# Power.net
KiCad netlist of a schematic drawn in Altium Designer
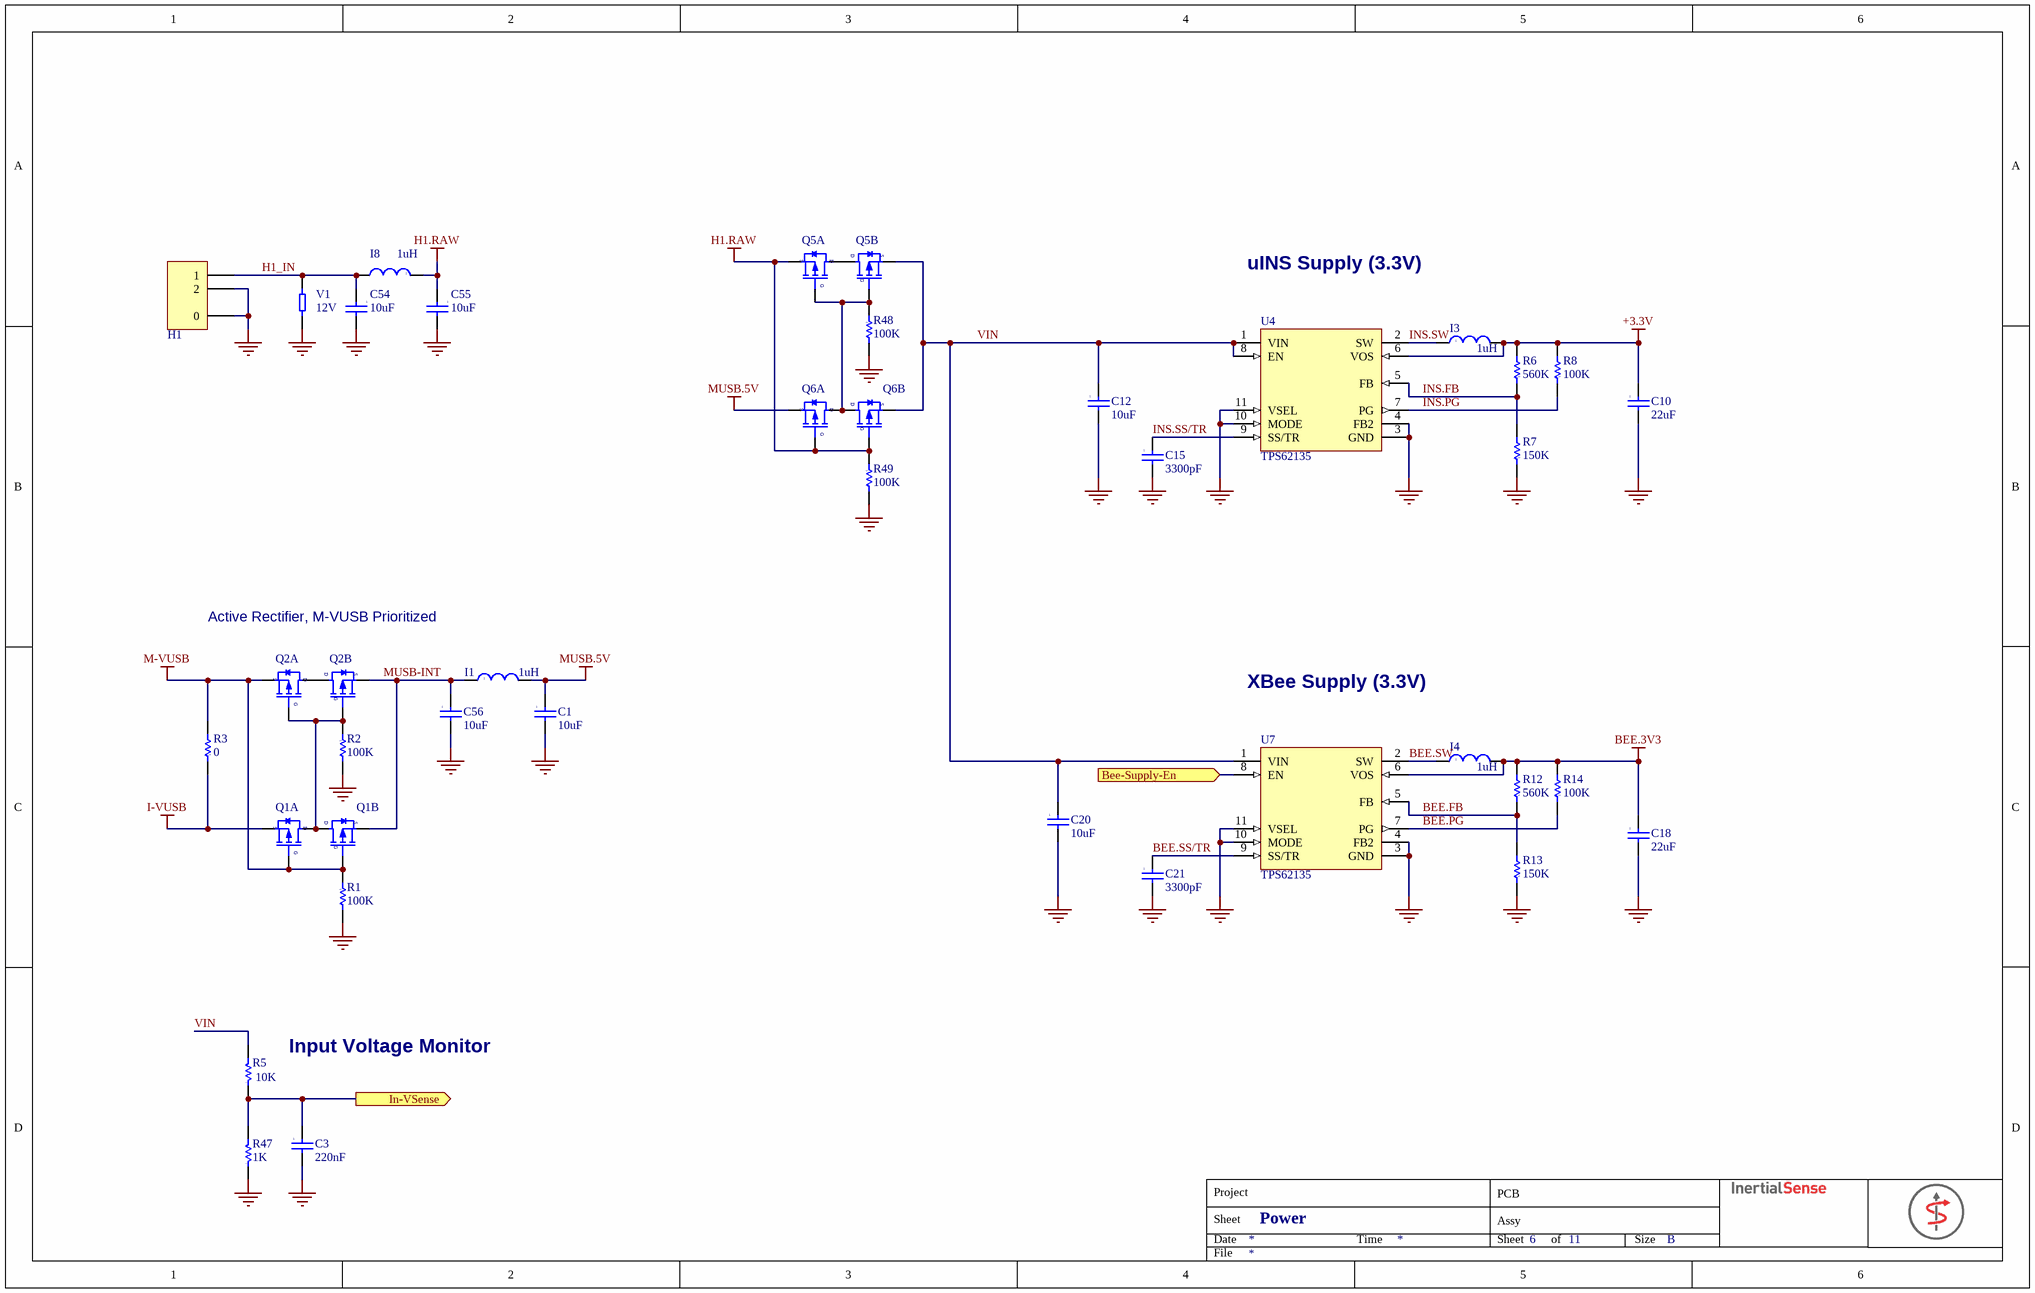
[diagram p0: Power.SchDoc]

(export (version "E")
  (design (tool "Eeschema 10.0.6"))
  (components
    (comp (ref "C1")
      (value "10uF")
      (footprint "0805")
      (description "CAP CER 10UF 35V X5R 0805")
      (fields
        (field (name "MANUFACTURER") "TDK")
        (field (name "MANUFACTURER PART NUMBER") "C2012X5R1V106K085AC")
        (field (name "PUBLISHER") "Altium Limited")
      )
      (libsource (lib "General") (part "Cap"))
    )
    (comp (ref "C3")
      (value "220nF")
      (footprint "0402")
      (description "CAP CER 0.22UF 16V X7R 0402")
      (fields
        (field (name "MANUFACTURER") "Murata")
        (field (name "MANUFACTURER PART NUMBER") "GRM155R71C224KA12D")
        (field (name "PUBLISHER") "Altium Limited")
      )
      (libsource (lib "General") (part "Cap"))
    )
    (comp (ref "C10")
      (value "22uF")
      (footprint "1206")
      (description "CAP CER 22UF 10V X5R 1206")
      (fields
        (field (name "MANUFACTURER") "Samsung")
        (field (name "MANUFACTURER PART NUMBER") "CL31A226KPHNNNE")
      )
      (libsource (lib "General") (part "Cap"))
    )
    (comp (ref "C12")
      (value "10uF")
      (footprint "0805")
      (description "CAP CER 10UF 35V X5R 0805")
      (fields
        (field (name "MANUFACTURER") "TDK")
        (field (name "MANUFACTURER PART NUMBER") "C2012X5R1V106K085AC")
        (field (name "PUBLISHER") "Altium Limited")
      )
      (libsource (lib "General") (part "Cap"))
    )
    (comp (ref "C15")
      (value "3300pF")
      (footprint "0402")
      (description "CAP CER 0.0033UF 50V X7R 0402")
      (fields
        (field (name "MANUFACTURER") "Samsung")
        (field (name "MANUFACTURER PART NUMBER") "CL05B332JB5NNNC")
      )
      (libsource (lib "General") (part "Cap"))
    )
    (comp (ref "C18")
      (value "22uF")
      (footprint "1206")
      (description "CAP CER 22UF 10V X5R 1206")
      (fields
        (field (name "MANUFACTURER") "Samsung")
        (field (name "MANUFACTURER PART NUMBER") "CL31A226KPHNNNE")
      )
      (libsource (lib "General") (part "Cap"))
    )
    (comp (ref "C20")
      (value "10uF")
      (footprint "0805")
      (description "CAP CER 10UF 35V X5R 0805")
      (fields
        (field (name "MANUFACTURER") "TDK")
        (field (name "MANUFACTURER PART NUMBER") "C2012X5R1V106K085AC")
        (field (name "PUBLISHER") "Altium Limited")
      )
      (libsource (lib "General") (part "Cap"))
    )
    (comp (ref "C21")
      (value "3300pF")
      (footprint "0402")
      (description "CAP CER 0.0033UF 50V X7R 0402")
      (fields
        (field (name "MANUFACTURER") "Samsung")
        (field (name "MANUFACTURER PART NUMBER") "CL05B332JB5NNNC")
      )
      (libsource (lib "General") (part "Cap"))
    )
    (comp (ref "C54")
      (value "10uF")
      (footprint "0805")
      (description "CAP CER 10UF 35V X5R 0805")
      (fields
        (field (name "MANUFACTURER") "TDK")
        (field (name "MANUFACTURER PART NUMBER") "C2012X5R1V106K085AC")
        (field (name "PUBLISHER") "Altium Limited")
      )
      (libsource (lib "General") (part "Cap"))
    )
    (comp (ref "C55")
      (value "10uF")
      (footprint "0805")
      (description "CAP CER 10UF 35V X5R 0805")
      (fields
        (field (name "MANUFACTURER") "TDK")
        (field (name "MANUFACTURER PART NUMBER") "C2012X5R1V106K085AC")
        (field (name "PUBLISHER") "Altium Limited")
      )
      (libsource (lib "General") (part "Cap"))
    )
    (comp (ref "C56")
      (value "10uF")
      (footprint "0805")
      (description "CAP CER 10UF 35V X5R 0805")
      (fields
        (field (name "MANUFACTURER") "TDK")
        (field (name "MANUFACTURER PART NUMBER") "C2012X5R1V106K085AC")
        (field (name "PUBLISHER") "Altium Limited")
      )
      (libsource (lib "General") (part "Cap"))
    )
    (comp (ref "H1")
      (value "Hdr - 2pin - mount")
      (footprint "S2B-PH-SM4-TB(LF)(SN)")
      (description "CONN HEADER PH SIDE 2POS 2MM SMD")
      (fields
        (field (name "MANUFACTURER") "JST")
        (field (name "MANUFACTURER PART NUMBER") "S2B-PH-SM4-TB(LF)(SN)")
      )
      (libsource (lib "Connectors") (part "Hdr - 2pin - mount"))
    )
    (comp (ref "I1")
      (value "1uH")
      (footprint "INDC2520X12N")
      (description "FIXED IND 1UH 3.3A 40 MOHM")
      (fields
        (field (name "MANUFACTURER") "Murata")
        (field (name "MANUFACTURER PART NUMBER") "DFE252012F-1R0M=P2")
      )
      (libsource (lib "General") (part "Inductor"))
    )
    (comp (ref "I3")
      (value "1uH")
      (footprint "INDC2520X12N")
      (description "FIXED IND 1UH 3.3A 40 MOHM")
      (fields
        (field (name "MANUFACTURER") "Murata")
        (field (name "MANUFACTURER PART NUMBER") "DFE252012F-1R0M=P2")
      )
      (libsource (lib "General") (part "Inductor"))
    )
    (comp (ref "I4")
      (value "1uH")
      (footprint "INDC2520X12N")
      (description "FIXED IND 1UH 3.3A 40 MOHM")
      (fields
        (field (name "MANUFACTURER") "Murata")
        (field (name "MANUFACTURER PART NUMBER") "DFE252012F-1R0M=P2")
      )
      (libsource (lib "General") (part "Inductor"))
    )
    (comp (ref "I8")
      (value "1uH")
      (footprint "INDC2520X12N")
      (description "FIXED IND 1UH 3.3A 40 MOHM")
      (fields
        (field (name "MANUFACTURER") "Murata")
        (field (name "MANUFACTURER PART NUMBER") "DFE252012F-1R0M=P2")
      )
      (libsource (lib "") (part "Inductor_1"))
    )
    (comp (ref "Q1")
      (value "MOSFET-P")
      (footprint "TSST8")
      (description "4V DRIVE PCH+PCH MOSFET")
      (fields (field (name "MANUFACTURER") "Rohm") (field (name "MANUFACTURER PART NUMBER") "TT8J3TR"))
      (libsource (lib "General") (part "MOSFET-Dual-P"))
    )
    (comp (ref "Q2")
      (value "MOSFET-P")
      (footprint "TSST8")
      (description "4V DRIVE PCH+PCH MOSFET")
      (fields (field (name "MANUFACTURER") "Rohm") (field (name "MANUFACTURER PART NUMBER") "TT8J3TR"))
      (libsource (lib "General") (part "MOSFET-Dual-P"))
    )
    (comp (ref "Q5")
      (value "MOSFET-P")
      (footprint "TSST8")
      (description "4V DRIVE PCH+PCH MOSFET")
      (fields (field (name "MANUFACTURER") "Rohm") (field (name "MANUFACTURER PART NUMBER") "TT8J3TR"))
      (libsource (lib "General") (part "MOSFET-Dual-P"))
    )
    (comp (ref "Q6")
      (value "MOSFET-P")
      (footprint "TSST8")
      (description "4V DRIVE PCH+PCH MOSFET")
      (fields (field (name "MANUFACTURER") "Rohm") (field (name "MANUFACTURER PART NUMBER") "TT8J3TR"))
      (libsource (lib "General") (part "MOSFET-Dual-P"))
    )
    (comp (ref "R1")
      (value "100K")
      (footprint "R0402")
      (description "RES SMD 100K OHM 1% 1/16W 0402")
      (fields
        (field (name "MANUFACTURER") "Panasonic")
        (field (name "MANUFACTURER PART NUMBER") "ERJ-2RKF1003X")
      )
      (libsource (lib "") (part "Res_1"))
    )
    (comp (ref "R2")
      (value "100K")
      (footprint "R0402")
      (description "RES SMD 100K OHM 1% 1/16W 0402")
      (fields
        (field (name "MANUFACTURER") "Panasonic")
        (field (name "MANUFACTURER PART NUMBER") "ERJ-2RKF1003X")
      )
      (libsource (lib "") (part "Res_1"))
    )
    (comp (ref "R3")
      (value "0")
      (footprint "R0603")
      (description "RES SMD 0 OHM JUMPER 1/10W 0603")
      (fields
        (field (name "MANUFACTURER") "Yageo")
        (field (name "MANUFACTURER PART NUMBER") "RC0603JR-070RL")
      )
      (libsource (lib "General") (part "Res"))
    )
    (comp (ref "R5")
      (value "10K")
      (footprint "R0402")
      (description "RES 10K OHM 1/16W 1% 0402 SMD")
      (fields
        (field (name "MANUFACTURER") "Panasonic")
        (field (name "MANUFACTURER PART NUMBER") "ERJ-2RKF1002X")
      )
      (libsource (lib "") (part "Res_1"))
    )
    (comp (ref "R6")
      (value "560K")
      (footprint "R0402")
      (description "RES SMD 560K OHM 1% 1/10W 0402")
      (fields
        (field (name "MANUFACTURER") "Panasonic")
        (field (name "MANUFACTURER PART NUMBER") "ERJ-2RKF5603X")
      )
      (libsource (lib "General") (part "Res"))
    )
    (comp (ref "R7")
      (value "150K")
      (footprint "R0402")
      (description "RES SMD 150K OHM 1% 1/10W 0402")
      (fields
        (field (name "MANUFACTURER") "Panasonic")
        (field (name "MANUFACTURER PART NUMBER") "ERJ-2RKF1503X")
      )
      (libsource (lib "General") (part "Res"))
    )
    (comp (ref "R8")
      (value "100K")
      (footprint "R0402")
      (description "RES SMD 100K OHM 1% 1/16W 0402")
      (fields
        (field (name "MANUFACTURER") "Panasonic")
        (field (name "MANUFACTURER PART NUMBER") "ERJ-2RKF1003X")
      )
      (libsource (lib "General") (part "Res"))
    )
    (comp (ref "R12")
      (value "560K")
      (footprint "R0402")
      (description "RES SMD 560K OHM 1% 1/10W 0402")
      (fields
        (field (name "MANUFACTURER") "Panasonic")
        (field (name "MANUFACTURER PART NUMBER") "ERJ-2RKF5603X")
      )
      (libsource (lib "General") (part "Res"))
    )
    (comp (ref "R13")
      (value "150K")
      (footprint "R0402")
      (description "RES SMD 150K OHM 1% 1/10W 0402")
      (fields
        (field (name "MANUFACTURER") "Panasonic")
        (field (name "MANUFACTURER PART NUMBER") "ERJ-2RKF1503X")
      )
      (libsource (lib "General") (part "Res"))
    )
    (comp (ref "R14")
      (value "100K")
      (footprint "R0402")
      (description "RES SMD 100K OHM 1% 1/16W 0402")
      (fields
        (field (name "MANUFACTURER") "Panasonic")
        (field (name "MANUFACTURER PART NUMBER") "ERJ-2RKF1003X")
      )
      (libsource (lib "General") (part "Res"))
    )
    (comp (ref "R47")
      (value "1K")
      (footprint "R0402")
      (description "RES 1.00K OHM 1/16W 1% 0402 SMD")
      (fields
        (field (name "MANUFACTURER") "Yageo")
        (field (name "MANUFACTURER PART NUMBER") "RC0402FR-071KL")
      )
      (libsource (lib "") (part "Res_1"))
    )
    (comp (ref "R48")
      (value "100K")
      (footprint "R0402")
      (description "RES SMD 100K OHM 1% 1/16W 0402")
      (fields
        (field (name "MANUFACTURER") "Panasonic")
        (field (name "MANUFACTURER PART NUMBER") "ERJ-2RKF1003X")
      )
      (libsource (lib "") (part "Res_1"))
    )
    (comp (ref "R49")
      (value "100K")
      (footprint "R0402")
      (description "RES SMD 100K OHM 1% 1/16W 0402")
      (fields
        (field (name "MANUFACTURER") "Panasonic")
        (field (name "MANUFACTURER PART NUMBER") "ERJ-2RKF1003X")
      )
      (libsource (lib "") (part "Res_1"))
    )
    (comp (ref "U4")
      (value "TPS62135")
      (footprint "PQFN50P200X300X100-14N")
      (description "IC REG BUCK ADJ 3.5A 11VQFN")
      (fields
        (field (name "MANUFACTURER") "Texas Instruments")
        (field (name "MANUFACTURER PART NUMBER") "TPS62135RGXR")
      )
      (libsource (lib "ICs") (part "TPS62135"))
    )
    (comp (ref "U7")
      (value "TPS62135")
      (footprint "PQFN50P200X300X100-14N")
      (description "IC REG BUCK ADJ 3.5A 11VQFN")
      (fields
        (field (name "MANUFACTURER") "Texas Instruments")
        (field (name "MANUFACTURER PART NUMBER") "TPS62135RGXR")
      )
      (libsource (lib "ICs") (part "TPS62135"))
    )
    (comp (ref "V1")
      (value "Var")
      (footprint "R0402")
      (description "VARISTOR 0402")
      (fields
        (field (name "MANUFACTURER") "Bourns")
        (field (name "MANUFACTURER PART NUMBER") "CG0402MLC-12LG")
        (field (name "VOLTAGE RATING (DC)") "12V")
      )
      (libsource (lib "General") (part "Var"))
    )
  )
  (nets
    (net (code "1") (name "+3.3V") (class "Default")
      (node (ref "C10") (pin "1") (pinfunction "1_1") (pintype "passive"))
      (node (ref "I3") (pin "2") (pinfunction "2_2") (pintype "passive"))
      (node (ref "R6") (pin "2") (pinfunction "2_2") (pintype "passive"))
      (node (ref "R8") (pin "2") (pinfunction "2_2") (pintype "passive"))
      (node (ref "U4") (pin "6") (pinfunction "VOS_6") (pintype "input"))
    )
    (net (code "2") (name "/BEE.FB") (class "Default")
      (node (ref "R12") (pin "1") (pinfunction "1_1") (pintype "passive"))
      (node (ref "R13") (pin "2") (pinfunction "2_2") (pintype "passive"))
      (node (ref "U7") (pin "5") (pinfunction "FB_5") (pintype "input"))
    )
    (net (code "3") (name "/BEE.PG") (class "Default")
      (node (ref "R14") (pin "1") (pinfunction "1_1") (pintype "passive"))
      (node (ref "U7") (pin "7") (pinfunction "PG_7") (pintype "output"))
    )
    (net (code "4") (name "/BEE.SS{slash}TR") (class "Default")
      (node (ref "C21") (pin "1") (pinfunction "1_1") (pintype "passive"))
      (node (ref "U7") (pin "9") (pinfunction "SS/TR_9") (pintype "input"))
    )
    (net (code "5") (name "/BEE.SW") (class "Default")
      (node (ref "I4") (pin "1") (pinfunction "1_1") (pintype "passive"))
      (node (ref "U7") (pin "2") (pinfunction "SW_2") (pintype "power_in"))
    )
    (net (code "6") (name "/Bee-Supply-En") (class "Default")
      (node (ref "U7") (pin "8") (pinfunction "EN_8") (pintype "input"))
    )
    (net (code "7") (name "/H1_IN") (class "Default")
      (node (ref "C54") (pin "1") (pinfunction "1_1") (pintype "passive"))
      (node (ref "H1") (pin "1") (pinfunction "1_1") (pintype "passive"))
      (node (ref "I8") (pin "2") (pinfunction "2_2") (pintype "passive"))
      (node (ref "V1") (pin "1") (pinfunction "1_1") (pintype "passive"))
    )
    (net (code "8") (name "/INS.FB") (class "Default")
      (node (ref "R6") (pin "1") (pinfunction "1_1") (pintype "passive"))
      (node (ref "R7") (pin "2") (pinfunction "2_2") (pintype "passive"))
      (node (ref "U4") (pin "5") (pinfunction "FB_5") (pintype "input"))
    )
    (net (code "9") (name "/INS.PG") (class "Default")
      (node (ref "R8") (pin "1") (pinfunction "1_1") (pintype "passive"))
      (node (ref "U4") (pin "7") (pinfunction "PG_7") (pintype "output"))
    )
    (net (code "10") (name "/INS.SS{slash}TR") (class "Default")
      (node (ref "C15") (pin "1") (pinfunction "1_1") (pintype "passive"))
      (node (ref "U4") (pin "9") (pinfunction "SS/TR_9") (pintype "input"))
    )
    (net (code "11") (name "/INS.SW") (class "Default")
      (node (ref "I3") (pin "1") (pinfunction "1_1") (pintype "passive"))
      (node (ref "U4") (pin "2") (pinfunction "SW_2") (pintype "power_in"))
    )
    (net (code "12") (name "/In-VSense") (class "Default")
      (node (ref "C3") (pin "1") (pinfunction "1_1") (pintype "passive"))
      (node (ref "R47") (pin "2") (pinfunction "2_2") (pintype "passive"))
      (node (ref "R5") (pin "1") (pinfunction "1_1") (pintype "passive"))
    )
    (net (code "13") (name "/MUSB-INT") (class "Default")
      (node (ref "C56") (pin "1") (pinfunction "1_1") (pintype "passive"))
      (node (ref "I1") (pin "1") (pinfunction "1_1") (pintype "passive"))
      (node (ref "Q1") (pin "S2") (pinfunction "S_S2") (pintype "passive"))
      (node (ref "Q2") (pin "S2") (pinfunction "S_S2") (pintype "passive"))
    )
    (net (code "14") (name "/VIN") (class "Default")
      (node (ref "C12") (pin "1") (pinfunction "1_1") (pintype "passive"))
      (node (ref "C20") (pin "1") (pinfunction "1_1") (pintype "passive"))
      (node (ref "Q5") (pin "S2") (pinfunction "S_S2") (pintype "passive"))
      (node (ref "Q6") (pin "S2") (pinfunction "S_S2") (pintype "passive"))
      (node (ref "R5") (pin "2") (pinfunction "2_2") (pintype "passive"))
      (node (ref "U4") (pin "1") (pinfunction "VIN_1") (pintype "power_in"))
      (node (ref "U4") (pin "8") (pinfunction "EN_8") (pintype "input"))
      (node (ref "U7") (pin "1") (pinfunction "VIN_1") (pintype "power_in"))
    )
    (net (code "15") (name "BEE.3V3") (class "Default")
      (node (ref "C18") (pin "1") (pinfunction "1_1") (pintype "passive"))
      (node (ref "I4") (pin "2") (pinfunction "2_2") (pintype "passive"))
      (node (ref "R12") (pin "2") (pinfunction "2_2") (pintype "passive"))
      (node (ref "R14") (pin "2") (pinfunction "2_2") (pintype "passive"))
      (node (ref "U7") (pin "6") (pinfunction "VOS_6") (pintype "input"))
    )
    (net (code "16") (name "GND") (class "Default")
      (node (ref "C1") (pin "2") (pinfunction "2_2") (pintype "passive"))
      (node (ref "C10") (pin "2") (pinfunction "2_2") (pintype "passive"))
      (node (ref "C12") (pin "2") (pinfunction "2_2") (pintype "passive"))
      (node (ref "C15") (pin "2") (pinfunction "2_2") (pintype "passive"))
      (node (ref "C18") (pin "2") (pinfunction "2_2") (pintype "passive"))
      (node (ref "C20") (pin "2") (pinfunction "2_2") (pintype "passive"))
      (node (ref "C21") (pin "2") (pinfunction "2_2") (pintype "passive"))
      (node (ref "C3") (pin "2") (pinfunction "2_2") (pintype "passive"))
      (node (ref "C54") (pin "2") (pinfunction "2_2") (pintype "passive"))
      (node (ref "C55") (pin "2") (pinfunction "2_2") (pintype "passive"))
      (node (ref "C56") (pin "2") (pinfunction "2_2") (pintype "passive"))
      (node (ref "H1") (pin "0") (pinfunction "0_0") (pintype "passive"))
      (node (ref "H1") (pin "2") (pinfunction "2_2") (pintype "passive"))
      (node (ref "R1") (pin "2") (pinfunction "2_2") (pintype "passive"))
      (node (ref "R13") (pin "1") (pinfunction "1_1") (pintype "passive"))
      (node (ref "R2") (pin "2") (pinfunction "2_2") (pintype "passive"))
      (node (ref "R47") (pin "1") (pinfunction "1_1") (pintype "passive"))
      (node (ref "R48") (pin "2") (pinfunction "2_2") (pintype "passive"))
      (node (ref "R49") (pin "2") (pinfunction "2_2") (pintype "passive"))
      (node (ref "R7") (pin "1") (pinfunction "1_1") (pintype "passive"))
      (node (ref "U4") (pin "10") (pinfunction "MODE_10") (pintype "input"))
      (node (ref "U4") (pin "11") (pinfunction "VSEL_11") (pintype "input"))
      (node (ref "U4") (pin "3") (pinfunction "GND_3") (pintype "power_in"))
      (node (ref "U4") (pin "4") (pinfunction "FB2_4") (pintype "passive"))
      (node (ref "U7") (pin "10") (pinfunction "MODE_10") (pintype "input"))
      (node (ref "U7") (pin "11") (pinfunction "VSEL_11") (pintype "input"))
      (node (ref "U7") (pin "3") (pinfunction "GND_3") (pintype "power_in"))
      (node (ref "U7") (pin "4") (pinfunction "FB2_4") (pintype "passive"))
      (node (ref "V1") (pin "2") (pinfunction "2_2") (pintype "passive"))
    )
    (net (code "17") (name "H1.RAW") (class "Default")
      (node (ref "C55") (pin "1") (pinfunction "1_1") (pintype "passive"))
      (node (ref "I8") (pin "1") (pinfunction "1_1") (pintype "passive"))
      (node (ref "Q5") (pin "S1") (pinfunction "S_S1") (pintype "passive"))
      (node (ref "Q6") (pin "G1") (pinfunction "G_G1") (pintype "passive"))
      (node (ref "Q6") (pin "G2") (pinfunction "G_G2") (pintype "passive"))
      (node (ref "R49") (pin "1") (pinfunction "1_1") (pintype "passive"))
    )
    (net (code "18") (name "I-VUSB") (class "Default")
      (node (ref "Q1") (pin "S1") (pinfunction "S_S1") (pintype "passive"))
      (node (ref "R3") (pin "1") (pinfunction "1_1") (pintype "passive"))
    )
    (net (code "19") (name "M-VUSB") (class "Default")
      (node (ref "Q1") (pin "G1") (pinfunction "G_G1") (pintype "passive"))
      (node (ref "Q1") (pin "G2") (pinfunction "G_G2") (pintype "passive"))
      (node (ref "Q2") (pin "S1") (pinfunction "S_S1") (pintype "passive"))
      (node (ref "R1") (pin "1") (pinfunction "1_1") (pintype "passive"))
      (node (ref "R3") (pin "2") (pinfunction "2_2") (pintype "passive"))
    )
    (net (code "20") (name "MUSB.5V") (class "Default")
      (node (ref "C1") (pin "1") (pinfunction "1_1") (pintype "passive"))
      (node (ref "I1") (pin "2") (pinfunction "2_2") (pintype "passive"))
      (node (ref "Q6") (pin "S1") (pinfunction "S_S1") (pintype "passive"))
    )
    (net (code "21") (name "Net-(Q1A-D)") (class "Default")
      (node (ref "Q1") (pin "D1") (pinfunction "D_D1") (pintype "passive"))
      (node (ref "Q1") (pin "D2") (pinfunction "D_D2") (pintype "passive"))
      (node (ref "Q2") (pin "G1") (pinfunction "G_G1") (pintype "passive"))
      (node (ref "Q2") (pin "G2") (pinfunction "G_G2") (pintype "passive"))
      (node (ref "R2") (pin "1") (pinfunction "1_1") (pintype "passive"))
    )
    (net (code "22") (name "Net-(Q2A-D)") (class "Default")
      (node (ref "Q2") (pin "D1") (pinfunction "D_D1") (pintype "passive"))
      (node (ref "Q2") (pin "D2") (pinfunction "D_D2") (pintype "passive"))
    )
    (net (code "23") (name "Net-(Q5A-D)") (class "Default")
      (node (ref "Q5") (pin "D1") (pinfunction "D_D1") (pintype "passive"))
      (node (ref "Q5") (pin "D2") (pinfunction "D_D2") (pintype "passive"))
    )
    (net (code "24") (name "Net-(Q5A-G)") (class "Default")
      (node (ref "Q5") (pin "G1") (pinfunction "G_G1") (pintype "passive"))
      (node (ref "Q5") (pin "G2") (pinfunction "G_G2") (pintype "passive"))
      (node (ref "Q6") (pin "D1") (pinfunction "D_D1") (pintype "passive"))
      (node (ref "Q6") (pin "D2") (pinfunction "D_D2") (pintype "passive"))
      (node (ref "R48") (pin "1") (pinfunction "1_1") (pintype "passive"))
    )
  )
)
